# fairy_lights_button.net
KiCad netlist of a schematic drawn in Altium Designer
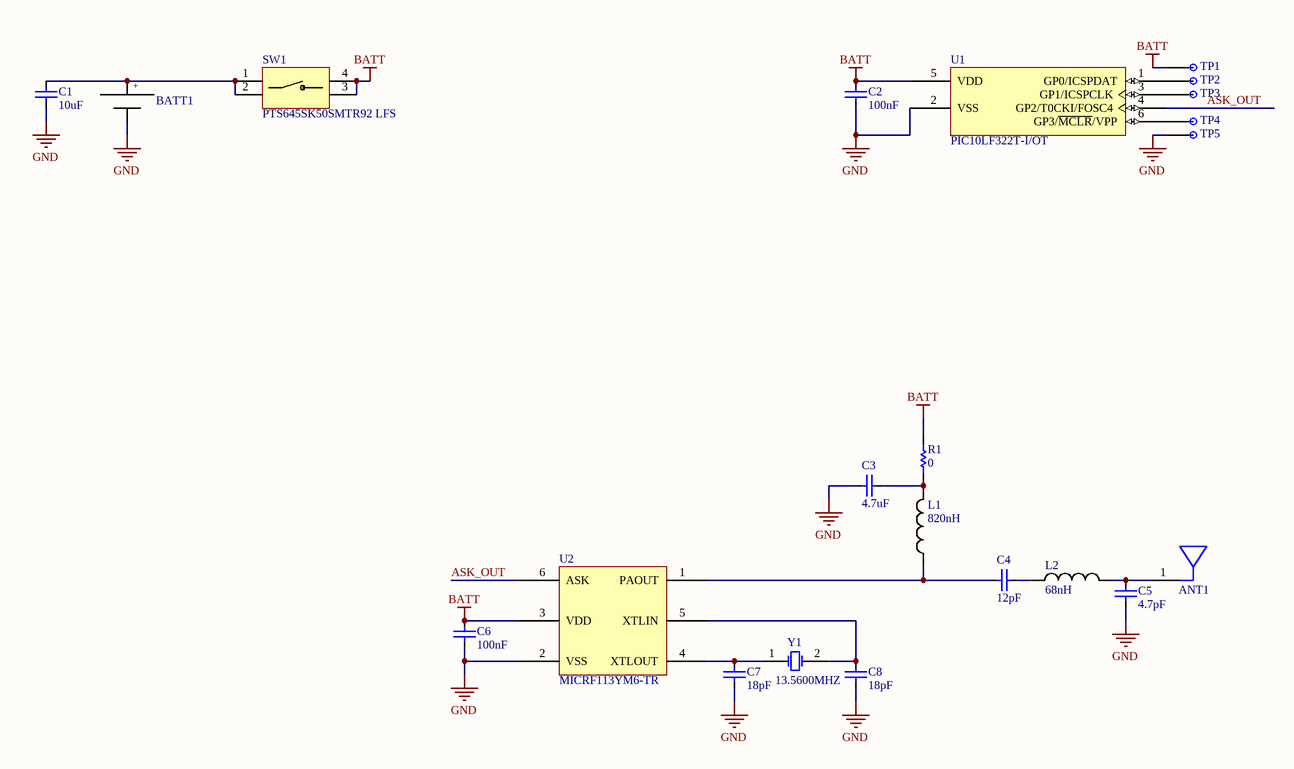
[diagram p0: fairy_lights_button.SchDoc]

(export (version "E")
  (design (tool "Eeschema 10.0.6"))
  (components
    (comp (ref "ANT1")
      (value "CHIP ANTENNA")
      (footprint "ANT-2.4-CHP")
      (description "Two terminal chip antenna")
      (libsource (lib "RUssery") (part "CHIP ANTENNA"))
    )
    (comp (ref "BATT1")
      (value "BAT-HLD-001")
      (footprint "BAT-HLD-001_BAT-HLD-001(Primary)")
      (description "CR2032 Phosphor Bronze / Nickel Plated 20 mm Cell Size Battery Holder")
      (libsource (lib "RUssery") (part "BAT-HLD-001"))
    )
    (comp (ref "C1")
      (value "10uF")
      (footprint "CAP_0805")
      (description "Capacitor")
      (libsource (lib "RUssery") (part "CAPACITOR"))
    )
    (comp (ref "C2")
      (value "100nF")
      (footprint "CAP_0603")
      (description "Capacitor")
      (libsource (lib "RUssery") (part "CAPACITOR"))
    )
    (comp (ref "C3")
      (value "4.7uF")
      (footprint "CAP_0603")
      (description "Capacitor")
      (libsource (lib "RUssery") (part "CAPACITOR"))
    )
    (comp (ref "C4")
      (value "12pF")
      (footprint "CAP_0603")
      (description "Capacitor")
      (libsource (lib "RUssery") (part "CAPACITOR"))
    )
    (comp (ref "C5")
      (value "4.7pF")
      (footprint "CAP_0603")
      (description "Capacitor")
      (libsource (lib "RUssery") (part "CAPACITOR"))
    )
    (comp (ref "C6")
      (value "100nF")
      (footprint "CAP_0603")
      (description "Capacitor")
      (libsource (lib "RUssery") (part "CAPACITOR"))
    )
    (comp (ref "C7") (value "18pF") (description "Capacitor") (libsource (lib "RUssery") (part "CAPACITOR")))
    (comp (ref "C8") (value "18pF") (description "Capacitor") (libsource (lib "RUssery") (part "CAPACITOR")))
    (comp (ref "L1")
      (value "LQW21HNR82J00L")
      (footprint "CAP_0805")
      (fields (field (name "INDUCTANCE") "820nH"))
      (libsource (lib "RUssery") (part "INDUCTOR"))
    )
    (comp (ref "L2")
      (value "LQW18AN68NJ00D")
      (footprint "CAP_0603")
      (fields (field (name "INDUCTANCE") "68nH"))
      (libsource (lib "RUssery") (part "INDUCTOR"))
    )
    (comp (ref "R1")
      (value "0")
      (footprint "RES_0603")
      (description "Resistor")
      (libsource (lib "RUssery") (part "RESISTOR"))
    )
    (comp (ref "SW1")
      (value "PTS645SK50SMTR92 LFS")
      (footprint "SWITCH_TACTILE_6MM")
      (description "SPST pushbutton - four terminal")
      (libsource (lib "RUssery") (part "PUSHBUTTON-SPST-4Term"))
    )
    (comp (ref "TP1")
      (value "TESTPOINT")
      (footprint "PAD_40MIL")
      (description "Test Point")
      (fields (field (name "PART NUMBER") "TestPoint SMT 40mil"))
      (libsource (lib "RUssery") (part "TESTPOINT"))
    )
    (comp (ref "TP2")
      (value "TESTPOINT")
      (footprint "PAD_40MIL")
      (description "Test Point")
      (fields (field (name "PART NUMBER") "TestPoint SMT 40mil"))
      (libsource (lib "RUssery") (part "TESTPOINT"))
    )
    (comp (ref "TP3")
      (value "TESTPOINT")
      (footprint "PAD_40MIL")
      (description "Test Point")
      (fields (field (name "PART NUMBER") "TestPoint SMT 40mil"))
      (libsource (lib "RUssery") (part "TESTPOINT"))
    )
    (comp (ref "TP4")
      (value "TESTPOINT")
      (footprint "PAD_40MIL")
      (description "Test Point")
      (fields (field (name "PART NUMBER") "TestPoint SMT 40mil"))
      (libsource (lib "RUssery") (part "TESTPOINT"))
    )
    (comp (ref "TP5")
      (value "TESTPOINT")
      (footprint "PAD_40MIL")
      (description "Test Point")
      (fields (field (name "PART NUMBER") "TestPoint SMT 40mil"))
      (libsource (lib "RUssery") (part "TESTPOINT"))
    )
    (comp (ref "U1")
      (value "PIC10LF322T-I/OT")
      (footprint "SOT-23-OT6_N")
      (description "PIC PIC® 10F Microcontroller IC 8-Bit 16MHz 896B (512 x 14) FLASH SOT-23-6")
      (libsource (lib "RUssery") (part "PIC10F202T"))
    )
    (comp (ref "U2")
      (value "MICRF113YM6-TR")
      (footprint "SOT-23-OT6_N")
      (description "RF Transmitter ASK 300MHz ~ 450MHz 10dBm 10 kbps PCB, Surface Mount Antenna SOT-23-6")
      (libsource (lib "RUssery") (part "MICRF113YM6-TR"))
    )
    (comp (ref "Y1")
      (value "ECS-135.6-20-3X-TR")
      (footprint "XTAL_ECS-135.6-20-3X-TR")
      (fields (field (name "FREQUENCY") "13.5600MHZ"))
      (libsource (lib "RUssery") (part "CRYSTAL"))
    )
  )
  (nets
    (net (code "1") (name "/ASK_OUT") (class "Default")
      (node (ref "U1") (pin "4") (pinfunction "GP2/T0CKI/FOSC4_4") (pintype "bidirectional"))
      (node (ref "U2") (pin "6") (pinfunction "ASK_6") (pintype "passive"))
    )
    (net (code "2") (name "BATT") (class "Default")
      (node (ref "C2") (pin "1") (pinfunction "1_1") (pintype "passive"))
      (node (ref "C6") (pin "1") (pinfunction "1_1") (pintype "passive"))
      (node (ref "R1") (pin "2") (pinfunction "2_2") (pintype "passive"))
      (node (ref "SW1") (pin "3") (pinfunction "3_3") (pintype "passive"))
      (node (ref "SW1") (pin "4") (pinfunction "4_4") (pintype "passive"))
      (node (ref "TP1") (pin "1") (pinfunction "1_1") (pintype "passive"))
      (node (ref "U1") (pin "5") (pinfunction "VDD_5") (pintype "power_in"))
      (node (ref "U2") (pin "3") (pinfunction "VDD_3") (pintype "passive"))
    )
    (net (code "3") (name "GND") (class "Default")
      (node (ref "BATT1") (pin "NEG") (pinfunction "NEG_NEG") (pintype "passive"))
      (node (ref "C1") (pin "2") (pinfunction "2_2") (pintype "passive"))
      (node (ref "C2") (pin "2") (pinfunction "2_2") (pintype "passive"))
      (node (ref "C3") (pin "1") (pinfunction "1_1") (pintype "passive"))
      (node (ref "C5") (pin "2") (pinfunction "2_2") (pintype "passive"))
      (node (ref "C6") (pin "2") (pinfunction "2_2") (pintype "passive"))
      (node (ref "C7") (pin "2") (pinfunction "2_2") (pintype "passive"))
      (node (ref "C8") (pin "2") (pinfunction "2_2") (pintype "passive"))
      (node (ref "TP5") (pin "1") (pinfunction "1_1") (pintype "passive"))
      (node (ref "U1") (pin "2") (pinfunction "VSS_2") (pintype "power_in"))
      (node (ref "U2") (pin "2") (pinfunction "VSS_2") (pintype "passive"))
    )
    (net (code "4") (name "Net-(ANT1-FEED)") (class "Default")
      (node (ref "ANT1") (pin "1") (pinfunction "FEED_1") (pintype "passive"))
      (node (ref "C5") (pin "1") (pinfunction "1_1") (pintype "passive"))
      (node (ref "L2") (pin "2") (pinfunction "2_2") (pintype "passive"))
    )
    (net (code "5") (name "Net-(BATT1-PadPOS1)") (class "Default")
      (node (ref "BATT1") (pin "POS1") (pintype "passive"))
      (node (ref "BATT1") (pin "POS2") (pintype "passive"))
      (node (ref "C1") (pin "1") (pinfunction "1_1") (pintype "passive"))
      (node (ref "SW1") (pin "1") (pinfunction "1_1") (pintype "passive"))
      (node (ref "SW1") (pin "2") (pinfunction "2_2") (pintype "passive"))
    )
    (net (code "6") (name "Net-(C3-Pad2)") (class "Default")
      (node (ref "C3") (pin "2") (pinfunction "2_2") (pintype "passive"))
      (node (ref "L1") (pin "2") (pinfunction "2_2") (pintype "passive"))
      (node (ref "R1") (pin "1") (pinfunction "1_1") (pintype "passive"))
    )
    (net (code "7") (name "Net-(C4-Pad2)") (class "Default")
      (node (ref "C4") (pin "2") (pinfunction "2_2") (pintype "passive"))
      (node (ref "L2") (pin "1") (pinfunction "1_1") (pintype "passive"))
    )
    (net (code "8") (name "Net-(U1-GP0{slash}ICSPDAT)") (class "Default")
      (node (ref "TP2") (pin "1") (pinfunction "1_1") (pintype "passive"))
      (node (ref "U1") (pin "1") (pinfunction "GP0/ICSPDAT_1") (pintype "bidirectional"))
    )
    (net (code "9") (name "Net-(U1-GP1{slash}ICSPCLK)") (class "Default")
      (node (ref "TP3") (pin "1") (pinfunction "1_1") (pintype "passive"))
      (node (ref "U1") (pin "3") (pinfunction "GP1/ICSPCLK_3") (pintype "bidirectional"))
    )
    (net (code "10") (name "Net-(U1-GP3{slash}~{MCLR}{slash}VPP)") (class "Default")
      (node (ref "TP4") (pin "1") (pinfunction "1_1") (pintype "passive"))
      (node (ref "U1") (pin "6") (pinfunction "GP3/~{MCLR}/VPP_6") (pintype "bidirectional"))
    )
    (net (code "11") (name "Net-(U2-PAOUT)") (class "Default")
      (node (ref "C4") (pin "1") (pinfunction "1_1") (pintype "passive"))
      (node (ref "L1") (pin "1") (pinfunction "1_1") (pintype "passive"))
      (node (ref "U2") (pin "1") (pinfunction "PAOUT_1") (pintype "passive"))
    )
    (net (code "12") (name "Net-(U2-XTLIN)") (class "Default")
      (node (ref "C8") (pin "1") (pinfunction "1_1") (pintype "passive"))
      (node (ref "U2") (pin "5") (pinfunction "XTLIN_5") (pintype "passive"))
      (node (ref "Y1") (pin "2") (pinfunction "X2_2") (pintype "passive"))
    )
    (net (code "13") (name "Net-(U2-XTLOUT)") (class "Default")
      (node (ref "C7") (pin "1") (pinfunction "1_1") (pintype "passive"))
      (node (ref "U2") (pin "4") (pinfunction "XTLOUT_4") (pintype "passive"))
      (node (ref "Y1") (pin "1") (pinfunction "X1_1") (pintype "passive"))
    )
    (net (code "14") (name "unconnected-(ANT1-NC-Pad2)") (class "Default")
      (node (ref "ANT1") (pin "2") (pinfunction "NC_2") (pintype "passive"))
    )
  )
)
